# MCU025B_XDS110_Target_Interface.net
KiCad netlist of a schematic drawn in Altium Designer
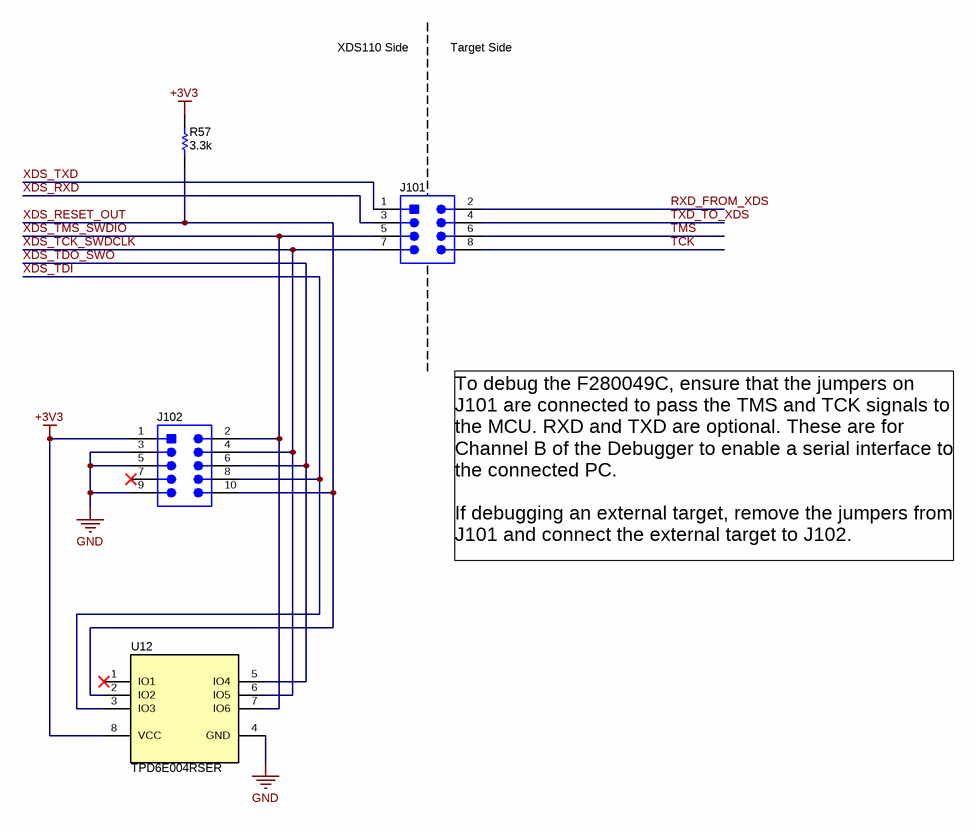
[diagram p0: MCU025B_XDS110_Target_Interface.SchDoc]

(export (version "E")
  (design (tool "Eeschema 10.0.6"))
  (components
    (comp (ref "J101")
      (value "TSW-104-07-G-D")
      (footprint "TSW-104-07-G-D")
      (description "Header, 100mil, 4x2, Gold, TH")
      (fields (field (name "MANUFACTURER") "Samtec") (field (name "PUBLISHER") "Texas Instruments"))
      (libsource (lib "Altium Vault - TI") (part "CMP-0075408-1"))
    )
    (comp (ref "J102")
      (value "FTSH-105-01-F-DV-K")
      (footprint "Samtec_FTSH-105-01-x-DV-K")
      (description "Header (Shrouded), 1.27mm, 5x2, Gold, SMT")
      (fields (field (name "MANUFACTURER") "Samtec") (field (name "PUBLISHER") "Texas Instruments"))
      (libsource (lib "Altium Vault - TI") (part "CMP-0075670-1"))
    )
    (comp (ref "R57")
      (value "CRCW04023K30JNED")
      (footprint "0402")
      (description "RES, 3.3 k, 5%, 0.063 W, AEC-Q200 Grade 0, 0402")
      (fields (field (name "VALUEDISPLAYED") "3.3k") (field (name "MANUFACTURER") "Vishay-Dale"))
      (libsource (lib "Altium Vault - TI") (part "Resistor"))
    )
    (comp (ref "U12")
      (value "TPD6E004RSER")
      (footprint "RSE0008A")
      (fields (field (name "MANUFACTURER") "Texas Instruments"))
      (libsource (lib "Altium Vault - TI") (part "TI-TPD6E004-UQFN_RSE-8"))
    )
  )
  (nets
    (net (code "1") (name "+3V3") (class "Default")
      (node (ref "J102") (pin "1") (pinfunction "1_1") (pintype "passive"))
      (node (ref "R57") (pin "2") (pinfunction "2_2") (pintype "passive"))
      (node (ref "U12") (pin "8") (pinfunction "VCC_8") (pintype "power_in"))
    )
    (net (code "2") (name "/RXD_FROM_XDS") (class "Default")
      (node (ref "J101") (pin "2") (pinfunction "2_2") (pintype "passive"))
    )
    (net (code "3") (name "/TCK") (class "Default")
      (node (ref "J101") (pin "8") (pinfunction "8_8") (pintype "passive"))
    )
    (net (code "4") (name "/TMS") (class "Default")
      (node (ref "J101") (pin "6") (pinfunction "6_6") (pintype "passive"))
    )
    (net (code "5") (name "/TXD_TO_XDS") (class "Default")
      (node (ref "J101") (pin "4") (pinfunction "4_4") (pintype "passive"))
    )
    (net (code "6") (name "/XDS_RESET_OUT") (class "Default")
      (node (ref "J102") (pin "10") (pinfunction "10_10") (pintype "passive"))
      (node (ref "R57") (pin "1") (pinfunction "1_1") (pintype "passive"))
      (node (ref "U12") (pin "2") (pinfunction "IO2_2") (pintype "passive"))
    )
    (net (code "7") (name "/XDS_RXD") (class "Default")
      (node (ref "J101") (pin "3") (pinfunction "3_3") (pintype "passive"))
    )
    (net (code "8") (name "/XDS_TCK_SWDCLK") (class "Default")
      (node (ref "J101") (pin "7") (pinfunction "7_7") (pintype "passive"))
      (node (ref "J102") (pin "4") (pinfunction "4_4") (pintype "passive"))
      (node (ref "U12") (pin "6") (pinfunction "IO5_6") (pintype "passive"))
    )
    (net (code "9") (name "/XDS_TDI") (class "Default")
      (node (ref "J102") (pin "8") (pinfunction "8_8") (pintype "passive"))
      (node (ref "U12") (pin "3") (pinfunction "IO3_3") (pintype "passive"))
    )
    (net (code "10") (name "/XDS_TDO_SWO") (class "Default")
      (node (ref "J102") (pin "6") (pinfunction "6_6") (pintype "passive"))
      (node (ref "U12") (pin "5") (pinfunction "IO4_5") (pintype "passive"))
    )
    (net (code "11") (name "/XDS_TMS_SWDIO") (class "Default")
      (node (ref "J101") (pin "5") (pinfunction "5_5") (pintype "passive"))
      (node (ref "J102") (pin "2") (pinfunction "2_2") (pintype "passive"))
      (node (ref "U12") (pin "7") (pinfunction "IO6_7") (pintype "passive"))
    )
    (net (code "12") (name "/XDS_TXD") (class "Default")
      (node (ref "J101") (pin "1") (pinfunction "1_1") (pintype "passive"))
    )
    (net (code "13") (name "GND") (class "Default")
      (node (ref "J102") (pin "3") (pinfunction "3_3") (pintype "passive"))
      (node (ref "J102") (pin "5") (pinfunction "5_5") (pintype "passive"))
      (node (ref "J102") (pin "9") (pinfunction "9_9") (pintype "passive"))
      (node (ref "U12") (pin "4") (pinfunction "GND_4") (pintype "power_in"))
    )
    (net (code "14") (name "unconnected-(J102-Pad7)") (class "Default")
      (node (ref "J102") (pin "7") (pinfunction "7_7") (pintype "passive+no_connect"))
    )
    (net (code "15") (name "unconnected-(U12-IO1-Pad1)") (class "Default")
      (node (ref "U12") (pin "1") (pinfunction "IO1_1") (pintype "passive+no_connect"))
    )
  )
)
